# ZB1.net
KiCad netlist of a schematic drawn in Altium Designer
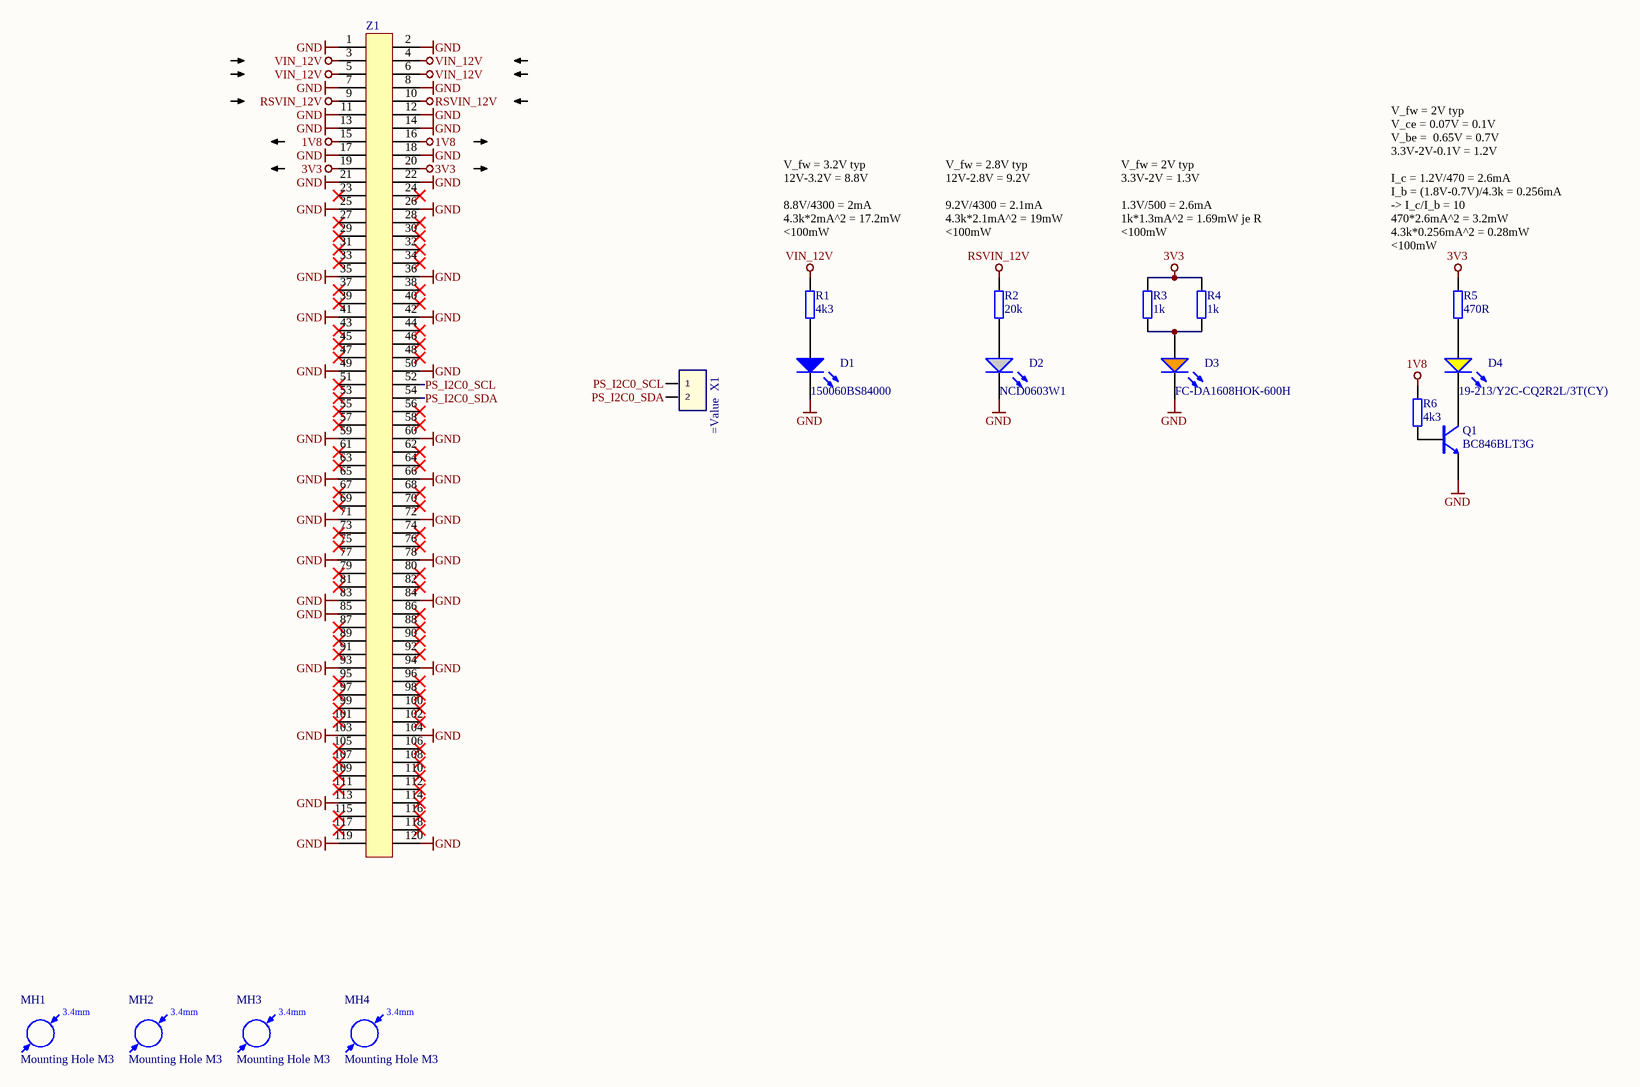
[diagram p0: ZB1.SchDoc]

(export (version "E")
  (design (tool "Eeschema 10.0.6"))
  (components
    (comp (ref "D1")
      (value "150060BS84000")
      (footprint "WL-SMCW_0603")
      (description "WL-SMCW SMD Mono-color Chip LED Waterclear Blue")
      (fields
        (field (name "MANUFACTURER") "Wuerth Elektronik")
        (field (name "LCSC PART NUMBER") "C5197644")
        (field (name "CREATED FROM") "MGremer")
      )
      (libsource (lib "user") (part "LED_Blue"))
    )
    (comp (ref "D2")
      (value "NCD0603W1")
      (footprint "WL-SMCW_0603")
      (description "White light 0603 Light Emitting Diodes (LED) ROHS")
      (fields
        (field (name "MANUFACTURER") "Foshan NationStar Optoelectronics")
        (field (name "LCSC PART NUMBER") "C84265")
        (field (name "CREATED FROM") "NDiringer")
      )
      (libsource (lib "user") (part "LED_White"))
    )
    (comp (ref "D3")
      (value "FC-DA1608HOK-600H")
      (footprint "WL-SMCW_0603")
      (description "LED ORANGE 600~610NM 80~220MCD@20MA TOP VIEW 0603 ROHS")
      (fields
        (field (name "MANUFACTURER") "Foshan NationStar Optoelectronics")
        (field (name "LCSC PART NUMBER") "C84269")
        (field (name "CREATED FROM") "T. Wendt")
      )
      (libsource (lib "user") (part "LED_Amber"))
    )
    (comp (ref "D4")
      (value "19-213/Y2C-CQ2R2L/3T(CY)")
      (footprint "WL-SMCW_0603")
      (description "LED YELLOW 585.5~591.5NM 90~180MCD@20MA TOP VIEW 0603 ROHS")
      (fields
        (field (name "MANUFACTURER") "Everlight Elec")
        (field (name "LCSC PART NUMBER") "C72038")
        (field (name "CREATED FROM") "T. Wendt")
      )
      (libsource (lib "user") (part "LED_Yellow"))
    )
    (comp (ref "MH1")
      (value "Mounting Hole M3")
      (footprint "MH_3.4")
      (description "Mounting Hole")
      (fields (field (name "CREATED FROM") "MHlatky"))
      (libsource (lib "user") (part "Mounting Hole"))
    )
    (comp (ref "MH2")
      (value "Mounting Hole M3")
      (footprint "MH_3.4")
      (description "Mounting Hole")
      (fields (field (name "CREATED FROM") "MHlatky"))
      (libsource (lib "user") (part "Mounting Hole"))
    )
    (comp (ref "MH3")
      (value "Mounting Hole M3")
      (footprint "MH_3.4")
      (description "Mounting Hole")
      (fields (field (name "CREATED FROM") "MHlatky"))
      (libsource (lib "user") (part "Mounting Hole"))
    )
    (comp (ref "MH4")
      (value "Mounting Hole M3")
      (footprint "MH_3.4")
      (description "Mounting Hole")
      (fields (field (name "CREATED FROM") "MHlatky"))
      (libsource (lib "user") (part "Mounting Hole"))
    )
    (comp (ref "Q1")
      (value "BC846BLT3G")
      (footprint "SOT95P280X145-3N")
      (description "Bipolartransistor, NPN 100mA 80V")
      (fields
        (field (name "MANUFACTURER") "onsemi")
        (field (name "LCSC PART NUMBER") "C513271")
        (field (name "CREATED FROM") "RWeimer")
      )
      (libsource (lib "user") (part "NPN-SOT23"))
    )
    (comp (ref "R1")
      (value "4k3")
      (footprint "RES 0603_1608")
      (description "SMD resistor E24 series")
      (fields
        (field (name "MANUFACTURER PART NUMBER") "RK73B1JTTD432J")
        (field (name "MANUFACTURER") "KOA Speer")
        (field (name "CREATED FROM") "MGremer")
      )
      (libsource (lib "user") (part "Resistor"))
    )
    (comp (ref "R2")
      (value "20k")
      (footprint "RES 0603_1608")
      (description "SMD resistor E24 series")
      (fields
        (field (name "MANUFACTURER PART NUMBER") "0603WAF2002T5E")
        (field (name "MANUFACTURER") "UNI-ROYAL")
        (field (name "CREATED FROM") "AGeiger")
      )
      (libsource (lib "user") (part "Resistor"))
    )
    (comp (ref "R3")
      (value "1k")
      (footprint "RES 0603_1608")
      (description "SMD resistor E24 series")
      (fields
        (field (name "MANUFACTURER PART NUMBER") "0603WAF1001T5E")
        (field (name "MANUFACTURER") "UNI-ROYAL")
        (field (name "CREATED FROM") "AGeiger")
      )
      (libsource (lib "user") (part "Resistor"))
    )
    (comp (ref "R4")
      (value "1k")
      (footprint "RES 0603_1608")
      (description "SMD resistor E24 series")
      (fields
        (field (name "MANUFACTURER PART NUMBER") "0603WAF1001T5E")
        (field (name "MANUFACTURER") "UNI-ROYAL")
        (field (name "CREATED FROM") "AGeiger")
      )
      (libsource (lib "user") (part "Resistor"))
    )
    (comp (ref "R5")
      (value "470R")
      (footprint "RES 0603_1608")
      (description "SMD resistor E24 series")
      (fields
        (field (name "MANUFACTURER PART NUMBER") "RK73B1JTTD471J")
        (field (name "MANUFACTURER") "KOA Speer")
        (field (name "CREATED FROM") "MGremer")
      )
      (libsource (lib "user") (part "Resistor"))
    )
    (comp (ref "R6")
      (value "4k3")
      (footprint "RES 0603_1608")
      (description "SMD resistor E24 series")
      (fields
        (field (name "MANUFACTURER PART NUMBER") "RK73B1JTTD432J")
        (field (name "MANUFACTURER") "KOA Speer")
        (field (name "CREATED FROM") "MGremer")
      )
      (libsource (lib "user") (part "Resistor"))
    )
    (comp (ref "X1")
      (value "~")
      (footprint "TSW-102-XX-XXX-S")
      (description "Classic PCB Header Strips, 0.100\" pitch")
      (fields
        (field (name "MANUFACTURER") "SAMTEC")
        (field (name "LCSC PART NUMBER") "C492401")
        (field (name "CREATED BY") "May 18, 2016 - Wendy Xin")
        (field (name "CREATED FROM") "AGeiger")
      )
      (libsource (lib "user") (part "TSW-102-XX-XXX-S"))
    )
    (comp (ref "Z1")
      (value "~")
      (footprint "ERM8-060-02.0-L-DV")
      (description "0.80 mm Edge Rate Rugged High Speed")
      (fields
        (field (name "MANUFACTURER PART NUMBER") "ERM8-060-02.0-L-DV-TR")
        (field (name "MANUFACTURER") "SAMTEC")
        (field (name "CREATED FROM") "AGeiger")
      )
      (libsource (lib "user") (part "CON-120"))
    )
  )
  (nets
    (net (code "1") (name "/PS_I2C0_SCL") (class "Default")
      (node (ref "X1") (pin "1") (pinfunction "1_1") (pintype "passive"))
      (node (ref "Z1") (pin "52") (pinfunction "52_52") (pintype "passive"))
    )
    (net (code "2") (name "/PS_I2C0_SDA") (class "Default")
      (node (ref "X1") (pin "2") (pinfunction "2_2") (pintype "passive"))
      (node (ref "Z1") (pin "54") (pinfunction "54_54") (pintype "passive"))
    )
    (net (code "3") (name "1V8") (class "Default")
      (node (ref "R6") (pin "2") (pinfunction "2_2") (pintype "passive"))
      (node (ref "Z1") (pin "15") (pinfunction "15_15") (pintype "passive"))
      (node (ref "Z1") (pin "16") (pinfunction "16_16") (pintype "passive"))
    )
    (net (code "4") (name "3V3") (class "Default")
      (node (ref "R3") (pin "2") (pinfunction "2_2") (pintype "passive"))
      (node (ref "R4") (pin "2") (pinfunction "2_2") (pintype "passive"))
      (node (ref "R5") (pin "2") (pinfunction "2_2") (pintype "passive"))
      (node (ref "Z1") (pin "19") (pinfunction "19_19") (pintype "passive"))
      (node (ref "Z1") (pin "20") (pinfunction "20_20") (pintype "passive"))
    )
    (net (code "5") (name "GND") (class "Default")
      (node (ref "D1") (pin "1") (pinfunction "K_1") (pintype "passive"))
      (node (ref "D2") (pin "1") (pinfunction "K_1") (pintype "passive"))
      (node (ref "D3") (pin "1") (pinfunction "K_1") (pintype "passive"))
      (node (ref "Q1") (pin "2") (pinfunction "EMITTER_2") (pintype "passive"))
      (node (ref "Z1") (pin "1") (pinfunction "1_1") (pintype "passive"))
      (node (ref "Z1") (pin "103") (pinfunction "103_103") (pintype "passive"))
      (node (ref "Z1") (pin "104") (pinfunction "104_104") (pintype "passive"))
      (node (ref "Z1") (pin "11") (pinfunction "11_11") (pintype "passive"))
      (node (ref "Z1") (pin "113") (pinfunction "113_113") (pintype "passive"))
      (node (ref "Z1") (pin "119") (pinfunction "119_119") (pintype "passive"))
      (node (ref "Z1") (pin "12") (pinfunction "12_12") (pintype "passive"))
      (node (ref "Z1") (pin "120") (pinfunction "120_120") (pintype "passive"))
      (node (ref "Z1") (pin "13") (pinfunction "13_13") (pintype "passive"))
      (node (ref "Z1") (pin "14") (pinfunction "14_14") (pintype "passive"))
      (node (ref "Z1") (pin "17") (pinfunction "17_17") (pintype "passive"))
      (node (ref "Z1") (pin "18") (pinfunction "18_18") (pintype "passive"))
      (node (ref "Z1") (pin "2") (pinfunction "2_2") (pintype "passive"))
      (node (ref "Z1") (pin "21") (pinfunction "21_21") (pintype "passive"))
      (node (ref "Z1") (pin "22") (pinfunction "22_22") (pintype "passive"))
      (node (ref "Z1") (pin "25") (pinfunction "25_25") (pintype "passive"))
      (node (ref "Z1") (pin "26") (pinfunction "26_26") (pintype "passive"))
      (node (ref "Z1") (pin "35") (pinfunction "35_35") (pintype "passive"))
      (node (ref "Z1") (pin "36") (pinfunction "36_36") (pintype "passive"))
      (node (ref "Z1") (pin "41") (pinfunction "41_41") (pintype "passive"))
      (node (ref "Z1") (pin "42") (pinfunction "42_42") (pintype "passive"))
      (node (ref "Z1") (pin "49") (pinfunction "49_49") (pintype "passive"))
      (node (ref "Z1") (pin "50") (pinfunction "50_50") (pintype "passive"))
      (node (ref "Z1") (pin "59") (pinfunction "59_59") (pintype "passive"))
      (node (ref "Z1") (pin "60") (pinfunction "60_60") (pintype "passive"))
      (node (ref "Z1") (pin "65") (pinfunction "65_65") (pintype "passive"))
      (node (ref "Z1") (pin "66") (pinfunction "66_66") (pintype "passive"))
      (node (ref "Z1") (pin "7") (pinfunction "7_7") (pintype "passive"))
      (node (ref "Z1") (pin "71") (pinfunction "71_71") (pintype "passive"))
      (node (ref "Z1") (pin "72") (pinfunction "72_72") (pintype "passive"))
      (node (ref "Z1") (pin "77") (pinfunction "77_77") (pintype "passive"))
      (node (ref "Z1") (pin "78") (pinfunction "78_78") (pintype "passive"))
      (node (ref "Z1") (pin "8") (pinfunction "8_8") (pintype "passive"))
      (node (ref "Z1") (pin "83") (pinfunction "83_83") (pintype "passive"))
      (node (ref "Z1") (pin "84") (pinfunction "84_84") (pintype "passive"))
      (node (ref "Z1") (pin "85") (pinfunction "85_85") (pintype "passive"))
      (node (ref "Z1") (pin "93") (pinfunction "93_93") (pintype "passive"))
      (node (ref "Z1") (pin "94") (pinfunction "94_94") (pintype "passive"))
    )
    (net (code "6") (name "Net-(D1-A)") (class "Default")
      (node (ref "D1") (pin "2") (pinfunction "A_2") (pintype "passive"))
      (node (ref "R1") (pin "1") (pinfunction "1_1") (pintype "passive"))
    )
    (net (code "7") (name "Net-(D2-A)") (class "Default")
      (node (ref "D2") (pin "2") (pinfunction "A_2") (pintype "passive"))
      (node (ref "R2") (pin "1") (pinfunction "1_1") (pintype "passive"))
    )
    (net (code "8") (name "Net-(D3-A)") (class "Default")
      (node (ref "D3") (pin "2") (pinfunction "A_2") (pintype "passive"))
      (node (ref "R3") (pin "1") (pinfunction "1_1") (pintype "passive"))
      (node (ref "R4") (pin "1") (pinfunction "1_1") (pintype "passive"))
    )
    (net (code "9") (name "Net-(D4-A)") (class "Default")
      (node (ref "D4") (pin "2") (pinfunction "A_2") (pintype "passive"))
      (node (ref "R5") (pin "1") (pinfunction "1_1") (pintype "passive"))
    )
    (net (code "10") (name "Net-(D4-K)") (class "Default")
      (node (ref "D4") (pin "1") (pinfunction "K_1") (pintype "passive"))
      (node (ref "Q1") (pin "3") (pinfunction "COLLECTOR_3") (pintype "passive"))
    )
    (net (code "11") (name "Net-(Q1-BASIS)") (class "Default")
      (node (ref "Q1") (pin "1") (pinfunction "BASIS_1") (pintype "passive"))
      (node (ref "R6") (pin "1") (pinfunction "1_1") (pintype "passive"))
    )
    (net (code "12") (name "RSVIN_12V") (class "Default")
      (node (ref "R2") (pin "2") (pinfunction "2_2") (pintype "passive"))
      (node (ref "Z1") (pin "10") (pinfunction "10_10") (pintype "passive"))
      (node (ref "Z1") (pin "9") (pinfunction "9_9") (pintype "passive"))
    )
    (net (code "13") (name "VIN_12V") (class "Default")
      (node (ref "R1") (pin "2") (pinfunction "2_2") (pintype "passive"))
      (node (ref "Z1") (pin "3") (pinfunction "3_3") (pintype "passive"))
      (node (ref "Z1") (pin "4") (pinfunction "4_4") (pintype "passive"))
      (node (ref "Z1") (pin "5") (pinfunction "5_5") (pintype "passive"))
      (node (ref "Z1") (pin "6") (pinfunction "6_6") (pintype "passive"))
    )
    (net (code "14") (name "unconnected-(Z1-Pad23)") (class "Default")
      (node (ref "Z1") (pin "23") (pinfunction "23_23") (pintype "passive+no_connect"))
    )
    (net (code "15") (name "unconnected-(Z1-Pad24)") (class "Default")
      (node (ref "Z1") (pin "24") (pinfunction "24_24") (pintype "passive+no_connect"))
    )
    (net (code "16") (name "unconnected-(Z1-Pad27)") (class "Default")
      (node (ref "Z1") (pin "27") (pinfunction "27_27") (pintype "passive+no_connect"))
    )
    (net (code "17") (name "unconnected-(Z1-Pad28)") (class "Default")
      (node (ref "Z1") (pin "28") (pinfunction "28_28") (pintype "passive+no_connect"))
    )
    (net (code "18") (name "unconnected-(Z1-Pad29)") (class "Default")
      (node (ref "Z1") (pin "29") (pinfunction "29_29") (pintype "passive+no_connect"))
    )
    (net (code "19") (name "unconnected-(Z1-Pad30)") (class "Default")
      (node (ref "Z1") (pin "30") (pinfunction "30_30") (pintype "passive+no_connect"))
    )
    (net (code "20") (name "unconnected-(Z1-Pad31)") (class "Default")
      (node (ref "Z1") (pin "31") (pinfunction "31_31") (pintype "passive+no_connect"))
    )
    (net (code "21") (name "unconnected-(Z1-Pad32)") (class "Default")
      (node (ref "Z1") (pin "32") (pinfunction "32_32") (pintype "passive+no_connect"))
    )
    (net (code "22") (name "unconnected-(Z1-Pad33)") (class "Default")
      (node (ref "Z1") (pin "33") (pinfunction "33_33") (pintype "passive+no_connect"))
    )
    (net (code "23") (name "unconnected-(Z1-Pad34)") (class "Default")
      (node (ref "Z1") (pin "34") (pinfunction "34_34") (pintype "passive+no_connect"))
    )
    (net (code "24") (name "unconnected-(Z1-Pad37)") (class "Default")
      (node (ref "Z1") (pin "37") (pinfunction "37_37") (pintype "passive+no_connect"))
    )
    (net (code "25") (name "unconnected-(Z1-Pad38)") (class "Default")
      (node (ref "Z1") (pin "38") (pinfunction "38_38") (pintype "passive+no_connect"))
    )
    (net (code "26") (name "unconnected-(Z1-Pad39)") (class "Default")
      (node (ref "Z1") (pin "39") (pinfunction "39_39") (pintype "passive+no_connect"))
    )
    (net (code "27") (name "unconnected-(Z1-Pad40)") (class "Default")
      (node (ref "Z1") (pin "40") (pinfunction "40_40") (pintype "passive+no_connect"))
    )
    (net (code "28") (name "unconnected-(Z1-Pad43)") (class "Default")
      (node (ref "Z1") (pin "43") (pinfunction "43_43") (pintype "passive+no_connect"))
    )
    (net (code "29") (name "unconnected-(Z1-Pad44)") (class "Default")
      (node (ref "Z1") (pin "44") (pinfunction "44_44") (pintype "passive+no_connect"))
    )
    (net (code "30") (name "unconnected-(Z1-Pad45)") (class "Default")
      (node (ref "Z1") (pin "45") (pinfunction "45_45") (pintype "passive+no_connect"))
    )
    (net (code "31") (name "unconnected-(Z1-Pad46)") (class "Default")
      (node (ref "Z1") (pin "46") (pinfunction "46_46") (pintype "passive+no_connect"))
    )
    (net (code "32") (name "unconnected-(Z1-Pad47)") (class "Default")
      (node (ref "Z1") (pin "47") (pinfunction "47_47") (pintype "passive+no_connect"))
    )
    (net (code "33") (name "unconnected-(Z1-Pad48)") (class "Default")
      (node (ref "Z1") (pin "48") (pinfunction "48_48") (pintype "passive+no_connect"))
    )
    (net (code "34") (name "unconnected-(Z1-Pad51)") (class "Default")
      (node (ref "Z1") (pin "51") (pinfunction "51_51") (pintype "passive+no_connect"))
    )
    (net (code "35") (name "unconnected-(Z1-Pad53)") (class "Default")
      (node (ref "Z1") (pin "53") (pinfunction "53_53") (pintype "passive+no_connect"))
    )
    (net (code "36") (name "unconnected-(Z1-Pad55)") (class "Default")
      (node (ref "Z1") (pin "55") (pinfunction "55_55") (pintype "passive+no_connect"))
    )
    (net (code "37") (name "unconnected-(Z1-Pad56)") (class "Default")
      (node (ref "Z1") (pin "56") (pinfunction "56_56") (pintype "passive+no_connect"))
    )
    (net (code "38") (name "unconnected-(Z1-Pad57)") (class "Default")
      (node (ref "Z1") (pin "57") (pinfunction "57_57") (pintype "passive+no_connect"))
    )
    (net (code "39") (name "unconnected-(Z1-Pad58)") (class "Default")
      (node (ref "Z1") (pin "58") (pinfunction "58_58") (pintype "passive+no_connect"))
    )
    (net (code "40") (name "unconnected-(Z1-Pad61)") (class "Default")
      (node (ref "Z1") (pin "61") (pinfunction "61_61") (pintype "passive+no_connect"))
    )
    (net (code "41") (name "unconnected-(Z1-Pad62)") (class "Default")
      (node (ref "Z1") (pin "62") (pinfunction "62_62") (pintype "passive+no_connect"))
    )
    (net (code "42") (name "unconnected-(Z1-Pad63)") (class "Default")
      (node (ref "Z1") (pin "63") (pinfunction "63_63") (pintype "passive+no_connect"))
    )
    (net (code "43") (name "unconnected-(Z1-Pad64)") (class "Default")
      (node (ref "Z1") (pin "64") (pinfunction "64_64") (pintype "passive+no_connect"))
    )
    (net (code "44") (name "unconnected-(Z1-Pad67)") (class "Default")
      (node (ref "Z1") (pin "67") (pinfunction "67_67") (pintype "passive+no_connect"))
    )
    (net (code "45") (name "unconnected-(Z1-Pad68)") (class "Default")
      (node (ref "Z1") (pin "68") (pinfunction "68_68") (pintype "passive+no_connect"))
    )
    (net (code "46") (name "unconnected-(Z1-Pad69)") (class "Default")
      (node (ref "Z1") (pin "69") (pinfunction "69_69") (pintype "passive+no_connect"))
    )
    (net (code "47") (name "unconnected-(Z1-Pad70)") (class "Default")
      (node (ref "Z1") (pin "70") (pinfunction "70_70") (pintype "passive+no_connect"))
    )
    (net (code "48") (name "unconnected-(Z1-Pad73)") (class "Default")
      (node (ref "Z1") (pin "73") (pinfunction "73_73") (pintype "passive+no_connect"))
    )
    (net (code "49") (name "unconnected-(Z1-Pad74)") (class "Default")
      (node (ref "Z1") (pin "74") (pinfunction "74_74") (pintype "passive+no_connect"))
    )
    (net (code "50") (name "unconnected-(Z1-Pad75)") (class "Default")
      (node (ref "Z1") (pin "75") (pinfunction "75_75") (pintype "passive+no_connect"))
    )
    (net (code "51") (name "unconnected-(Z1-Pad76)") (class "Default")
      (node (ref "Z1") (pin "76") (pinfunction "76_76") (pintype "passive+no_connect"))
    )
    (net (code "52") (name "unconnected-(Z1-Pad79)") (class "Default")
      (node (ref "Z1") (pin "79") (pinfunction "79_79") (pintype "passive+no_connect"))
    )
    (net (code "53") (name "unconnected-(Z1-Pad80)") (class "Default")
      (node (ref "Z1") (pin "80") (pinfunction "80_80") (pintype "passive+no_connect"))
    )
    (net (code "54") (name "unconnected-(Z1-Pad81)") (class "Default")
      (node (ref "Z1") (pin "81") (pinfunction "81_81") (pintype "passive+no_connect"))
    )
    (net (code "55") (name "unconnected-(Z1-Pad82)") (class "Default")
      (node (ref "Z1") (pin "82") (pinfunction "82_82") (pintype "passive+no_connect"))
    )
    (net (code "56") (name "unconnected-(Z1-Pad86)") (class "Default")
      (node (ref "Z1") (pin "86") (pinfunction "86_86") (pintype "passive+no_connect"))
    )
    (net (code "57") (name "unconnected-(Z1-Pad87)") (class "Default")
      (node (ref "Z1") (pin "87") (pinfunction "87_87") (pintype "passive+no_connect"))
    )
    (net (code "58") (name "unconnected-(Z1-Pad88)") (class "Default")
      (node (ref "Z1") (pin "88") (pinfunction "88_88") (pintype "passive+no_connect"))
    )
    (net (code "59") (name "unconnected-(Z1-Pad89)") (class "Default")
      (node (ref "Z1") (pin "89") (pinfunction "89_89") (pintype "passive+no_connect"))
    )
    (net (code "60") (name "unconnected-(Z1-Pad90)") (class "Default")
      (node (ref "Z1") (pin "90") (pinfunction "90_90") (pintype "passive+no_connect"))
    )
    (net (code "61") (name "unconnected-(Z1-Pad91)") (class "Default")
      (node (ref "Z1") (pin "91") (pinfunction "91_91") (pintype "passive+no_connect"))
    )
    (net (code "62") (name "unconnected-(Z1-Pad92)") (class "Default")
      (node (ref "Z1") (pin "92") (pinfunction "92_92") (pintype "passive+no_connect"))
    )
    (net (code "63") (name "unconnected-(Z1-Pad95)") (class "Default")
      (node (ref "Z1") (pin "95") (pinfunction "95_95") (pintype "passive+no_connect"))
    )
    (net (code "64") (name "unconnected-(Z1-Pad96)") (class "Default")
      (node (ref "Z1") (pin "96") (pinfunction "96_96") (pintype "passive+no_connect"))
    )
    (net (code "65") (name "unconnected-(Z1-Pad97)") (class "Default")
      (node (ref "Z1") (pin "97") (pinfunction "97_97") (pintype "passive+no_connect"))
    )
    (net (code "66") (name "unconnected-(Z1-Pad98)") (class "Default")
      (node (ref "Z1") (pin "98") (pinfunction "98_98") (pintype "passive+no_connect"))
    )
    (net (code "67") (name "unconnected-(Z1-Pad99)") (class "Default")
      (node (ref "Z1") (pin "99") (pinfunction "99_99") (pintype "passive+no_connect"))
    )
    (net (code "68") (name "unconnected-(Z1-Pad100)") (class "Default")
      (node (ref "Z1") (pin "100") (pinfunction "100_100") (pintype "passive+no_connect"))
    )
    (net (code "69") (name "unconnected-(Z1-Pad101)") (class "Default")
      (node (ref "Z1") (pin "101") (pinfunction "101_101") (pintype "passive+no_connect"))
    )
    (net (code "70") (name "unconnected-(Z1-Pad102)") (class "Default")
      (node (ref "Z1") (pin "102") (pinfunction "102_102") (pintype "passive+no_connect"))
    )
    (net (code "71") (name "unconnected-(Z1-Pad105)") (class "Default")
      (node (ref "Z1") (pin "105") (pinfunction "105_105") (pintype "passive+no_connect"))
    )
    (net (code "72") (name "unconnected-(Z1-Pad106)") (class "Default")
      (node (ref "Z1") (pin "106") (pinfunction "106_106") (pintype "passive+no_connect"))
    )
    (net (code "73") (name "unconnected-(Z1-Pad107)") (class "Default")
      (node (ref "Z1") (pin "107") (pinfunction "107_107") (pintype "passive+no_connect"))
    )
    (net (code "74") (name "unconnected-(Z1-Pad108)") (class "Default")
      (node (ref "Z1") (pin "108") (pinfunction "108_108") (pintype "passive+no_connect"))
    )
    (net (code "75") (name "unconnected-(Z1-Pad109)") (class "Default")
      (node (ref "Z1") (pin "109") (pinfunction "109_109") (pintype "passive+no_connect"))
    )
    (net (code "76") (name "unconnected-(Z1-Pad110)") (class "Default")
      (node (ref "Z1") (pin "110") (pinfunction "110_110") (pintype "passive+no_connect"))
    )
    (net (code "77") (name "unconnected-(Z1-Pad111)") (class "Default")
      (node (ref "Z1") (pin "111") (pinfunction "111_111") (pintype "passive+no_connect"))
    )
    (net (code "78") (name "unconnected-(Z1-Pad112)") (class "Default")
      (node (ref "Z1") (pin "112") (pinfunction "112_112") (pintype "passive+no_connect"))
    )
    (net (code "79") (name "unconnected-(Z1-Pad114)") (class "Default")
      (node (ref "Z1") (pin "114") (pinfunction "114_114") (pintype "passive+no_connect"))
    )
    (net (code "80") (name "unconnected-(Z1-Pad115)") (class "Default")
      (node (ref "Z1") (pin "115") (pinfunction "115_115") (pintype "passive+no_connect"))
    )
    (net (code "81") (name "unconnected-(Z1-Pad116)") (class "Default")
      (node (ref "Z1") (pin "116") (pinfunction "116_116") (pintype "passive+no_connect"))
    )
    (net (code "82") (name "unconnected-(Z1-Pad117)") (class "Default")
      (node (ref "Z1") (pin "117") (pinfunction "117_117") (pintype "passive+no_connect"))
    )
    (net (code "83") (name "unconnected-(Z1-Pad118)") (class "Default")
      (node (ref "Z1") (pin "118") (pinfunction "118_118") (pintype "passive+no_connect"))
    )
  )
)
